# BMS-S07-V00-PSU.net
KiCad netlist of a schematic drawn in Altium Designer
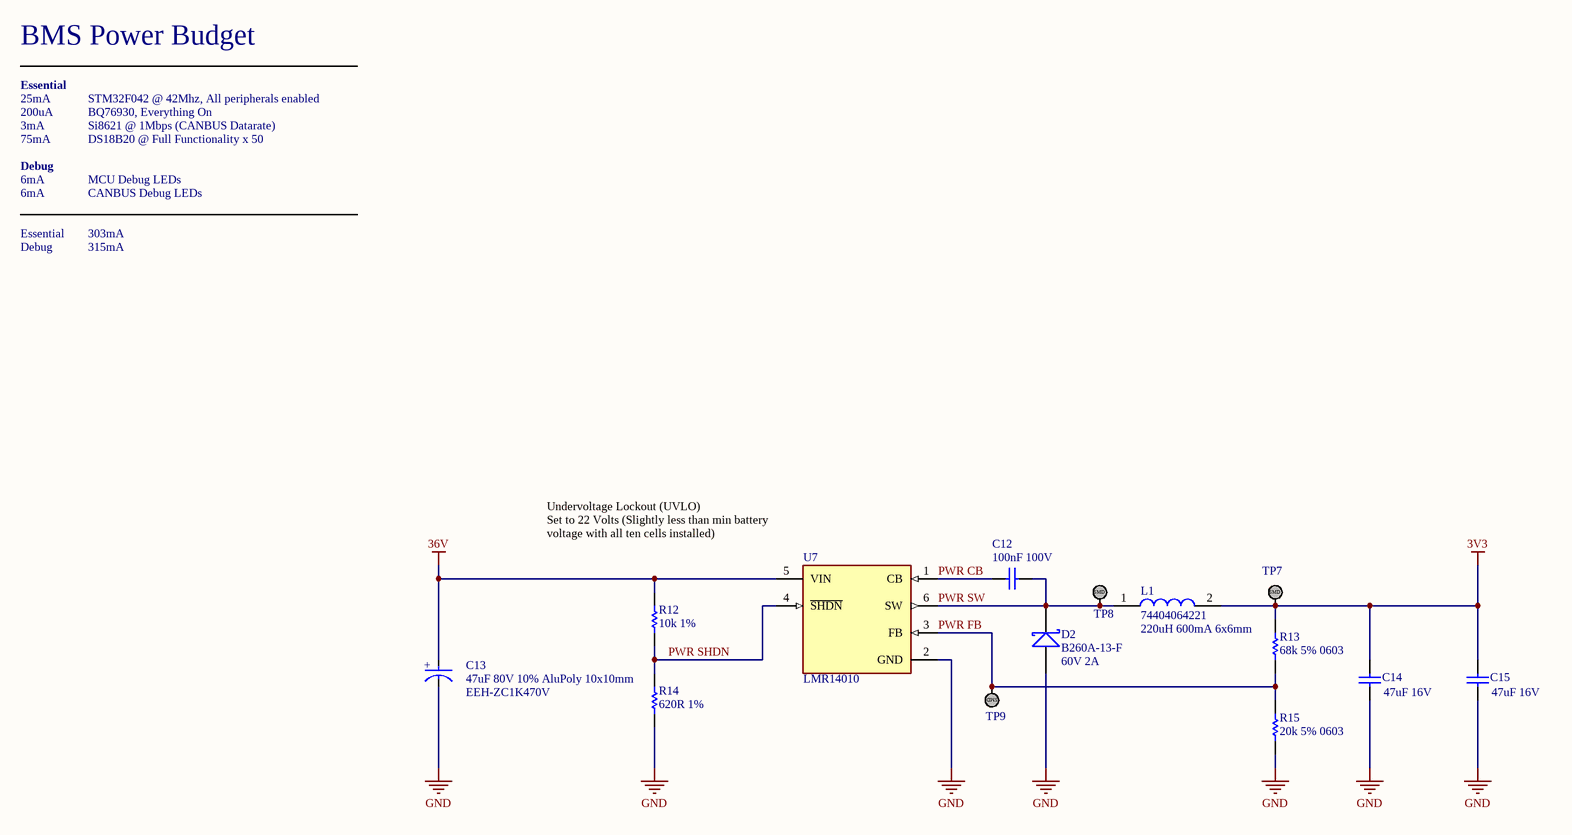
[diagram p0: BMS-S07-V00-PSU.SchDoc]

(export (version "E")
  (design (tool "Eeschema 10.0.6"))
  (components
    (comp (ref "C12")
      (value "100nF 100V")
      (footprint "Cap_Ceramic_0603")
      (description "Capacitor, Ceramic, SMD, 100nF, 100V, 5%, X7R, 0603")
      (libsource (lib "StandardCapacitors") (part "100nF 100V 5% X7R 0603"))
    )
    (comp (ref "C13")
      (value "47uF 80V 10% AluPoly 10x10mm")
      (footprint "CAP_ALU_10x10mm")
      (description "Capacitor, AluPoly, SMD, 47uF, 80V, 10%, AluPoly, 10x10mm")
      (libsource (lib "StandardCapacitors") (part "47uF 80V 10% AluPoly 10x10mm"))
    )
    (comp (ref "C14")
      (value "47uF 16V")
      (footprint "Cap_Ceramic_1210")
      (description "Capacitor, Ceramic, SMD, 47uF, 16V, 5%, X7R, 1210")
      (libsource (lib "StandardCapacitors") (part "47uF 16V 10% X7R 1210"))
    )
    (comp (ref "C15")
      (value "47uF 16V")
      (footprint "Cap_Ceramic_1210")
      (description "Capacitor, Ceramic, SMD, 47uF, 16V, 5%, X7R, 1210")
      (libsource (lib "StandardCapacitors") (part "47uF 16V 10% X7R 1210"))
    )
    (comp (ref "D2")
      (value "B260A-13-F")
      (footprint "SMA")
      (description "Diode, Schottky Barrier Rectifier, 60 V, 2 A, B260A-13-F")
      (libsource (lib "QUTMS_DiodeLibrary") (part "B260A-13-F"))
    )
    (comp (ref "L1")
      (value "74404064221")
      (footprint "Inductor_6x6mm")
      (description "FIXED IND 220UH 660MA 850 MOHM")
      (libsource (lib "QUTMS_InductorLibrary") (part "74404064221"))
    )
    (comp (ref "R12")
      (value "10k 1%")
      (footprint "Res_ThinFilm_0603")
      (description "Resistor, SMD, 10k, 0.1W, 1%, 0603")
      (libsource (lib "StandardResistors") (part "10k 1% 0603"))
    )
    (comp (ref "R13")
      (value "68k 5% 0603")
      (footprint "Res_ThinFilm_0603")
      (description "Resistor, SMD, 68k, 0.1W, 5%, 0603")
      (libsource (lib "StandardResistors") (part "68k 5% 0603"))
    )
    (comp (ref "R14")
      (value "620R 1%")
      (footprint "Res_ThinFilm_0603")
      (description "Resistor, SMD, 680R, 0.1W, 5%, 0603")
      (libsource (lib "StandardResistors") (part "620R 1% 0603"))
    )
    (comp (ref "R15")
      (value "20k 5% 0603")
      (footprint "Res_ThinFilm_0603")
      (description "Resistor, SMD, 20k, 0.1W, 5%, 0603")
      (libsource (lib "StandardResistors") (part "20k 5% 0603"))
    )
    (comp (ref "TP7")
      (value "TestPoint_SMD")
      (footprint "TestPointSMD")
      (libsource (lib "StandardTest") (part "TestPoint_SMD"))
    )
    (comp (ref "TP8")
      (value "TestPoint_SMD")
      (footprint "TestPointSMD")
      (libsource (lib "StandardTest") (part "TestPoint_SMD"))
    )
    (comp (ref "TP9")
      (value "TestPoint_SMD")
      (footprint "TestPointSMD")
      (libsource (lib "StandardTest") (part "TestPoint_SMD"))
    )
    (comp (ref "U7")
      (value "LMR14010")
      (footprint "LMR14010")
      (libsource (lib "QUTMS_PowerSupplyLibrary") (part "LMR14010"))
    )
  )
  (nets
    (net (code "1") (name "/PWR CB") (class "Default")
      (node (ref "C12") (pin "1") (pinfunction "1_1") (pintype "passive"))
      (node (ref "U7") (pin "1") (pinfunction "CB_1") (pintype "input"))
    )
    (net (code "2") (name "/PWR FB") (class "Default")
      (node (ref "R13") (pin "1") (pinfunction "1_1") (pintype "passive"))
      (node (ref "R15") (pin "2") (pinfunction "2_2") (pintype "passive"))
      (node (ref "TP9") (pin "1") (pinfunction "1_1") (pintype "passive"))
      (node (ref "U7") (pin "3") (pinfunction "FB_3") (pintype "input"))
    )
    (net (code "3") (name "/PWR SHDN") (class "Default")
      (node (ref "R12") (pin "1") (pinfunction "1_1") (pintype "passive"))
      (node (ref "R14") (pin "2") (pinfunction "2_2") (pintype "passive"))
      (node (ref "U7") (pin "4") (pinfunction "~{SHDN}_4") (pintype "input"))
    )
    (net (code "4") (name "/PWR SW") (class "Default")
      (node (ref "C12") (pin "2") (pinfunction "2_2") (pintype "passive"))
      (node (ref "D2") (pin "K") (pinfunction "K_K") (pintype "passive"))
      (node (ref "L1") (pin "1") (pinfunction "1_1") (pintype "passive"))
      (node (ref "TP8") (pin "1") (pinfunction "1_1") (pintype "passive"))
      (node (ref "U7") (pin "6") (pinfunction "SW_6") (pintype "output"))
    )
    (net (code "5") (name "3V3") (class "Default")
      (node (ref "C14") (pin "2") (pinfunction "2_2") (pintype "passive"))
      (node (ref "C15") (pin "2") (pinfunction "2_2") (pintype "passive"))
      (node (ref "L1") (pin "2") (pinfunction "2_2") (pintype "passive"))
      (node (ref "R13") (pin "2") (pinfunction "2_2") (pintype "passive"))
      (node (ref "TP7") (pin "1") (pinfunction "1_1") (pintype "passive"))
    )
    (net (code "6") (name "36V") (class "Default")
      (node (ref "C13") (pin "A") (pinfunction "A_A") (pintype "passive"))
      (node (ref "R12") (pin "2") (pinfunction "2_2") (pintype "passive"))
      (node (ref "U7") (pin "5") (pinfunction "VIN_5") (pintype "power_in"))
    )
    (net (code "7") (name "GND") (class "Default")
      (node (ref "C13") (pin "K") (pinfunction "K_K") (pintype "passive"))
      (node (ref "C14") (pin "1") (pinfunction "1_1") (pintype "passive"))
      (node (ref "C15") (pin "1") (pinfunction "1_1") (pintype "passive"))
      (node (ref "D2") (pin "A") (pinfunction "A_A") (pintype "passive"))
      (node (ref "R14") (pin "1") (pinfunction "1_1") (pintype "passive"))
      (node (ref "R15") (pin "1") (pinfunction "1_1") (pintype "passive"))
      (node (ref "U7") (pin "2") (pinfunction "GND_2") (pintype "power_in"))
    )
  )
)
